# LPCB218_-_PARK_BRAKE.net
KiCad netlist of a schematic drawn in Altium Designer
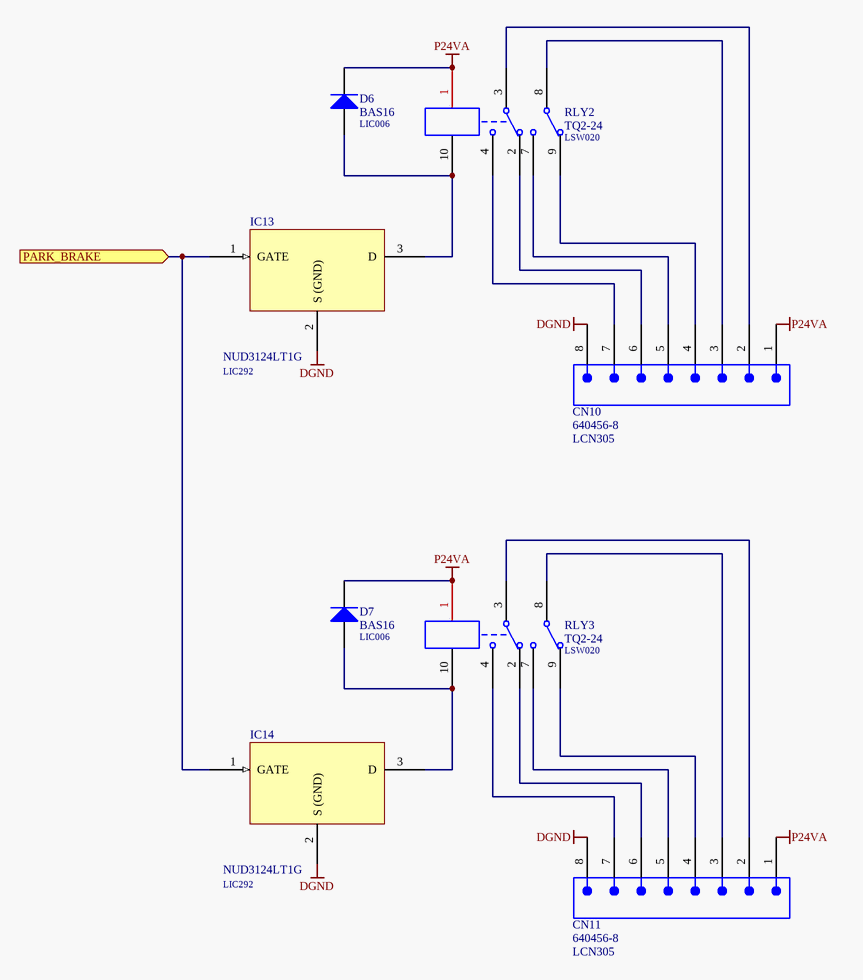
[diagram p0: LPCB218 - PARK BRAKE.SchDoc]

(export (version "E")
  (design (tool "Eeschema 10.0.6"))
  (components
    (comp (ref "CN10")
      (value "640456-8")
      (footprint "640456-8")
      (description "Connector, Male Header, 8 Way")
      (fields (field (name "LDL_NUMBER") "LCN305"))
      (libsource (lib "LDL_Connectors") (part "640456-8"))
    )
    (comp (ref "CN11")
      (value "640456-8")
      (footprint "640456-8")
      (description "Connector, Male Header, 8 Way")
      (fields (field (name "LDL_NUMBER") "LCN305"))
      (libsource (lib "LDL_Connectors") (part "640456-8"))
    )
    (comp (ref "D6")
      (value "BAS16")
      (footprint "LFP021__SOT23")
      (description "Diode, Small Signal, 0.2A, 85V, SMD SOT-23 [LIC006]")
      (fields (field (name "LDL_NUMBER") "LIC006"))
      (libsource (lib "LDL_Semiconductors") (part "BAS16"))
    )
    (comp (ref "D7")
      (value "BAS16")
      (footprint "LFP021__SOT23")
      (description "Diode, Small Signal, 0.2A, 85V, SMD SOT-23 [LIC006]")
      (fields (field (name "LDL_NUMBER") "LIC006"))
      (libsource (lib "LDL_Semiconductors") (part "BAS16"))
    )
    (comp (ref "IC13")
      (value "NUD3124LT1G")
      (footprint "LFP021__SOT23")
      (description "IC, Relay Driver, 28V Industrial, SMD SOT23 [LIC292]")
      (fields (field (name "LDL_NUMBER") "LIC292"))
      (libsource (lib "LDL_Semiconductors") (part "NUD3124LT1G"))
    )
    (comp (ref "IC14")
      (value "NUD3124LT1G")
      (footprint "LFP021__SOT23")
      (description "IC, Relay Driver, 28V Industrial, SMD SOT23 [LIC292]")
      (fields (field (name "LDL_NUMBER") "LIC292"))
      (libsource (lib "LDL_Semiconductors") (part "NUD3124LT1G"))
    )
    (comp (ref "RLY2")
      (value "TQ2-24")
      (footprint "TQ2")
      (description "Relay, DPDT, Non Latching, 24VDC Coil, 1A Rating, PTH")
      (fields (field (name "LDL_NUMBER") "LSW020"))
      (libsource (lib "LDL_Switching") (part "TQ2-24"))
    )
    (comp (ref "RLY3")
      (value "TQ2-24")
      (footprint "TQ2")
      (description "Relay, DPDT, Non Latching, 24VDC Coil, 1A Rating, PTH")
      (fields (field (name "LDL_NUMBER") "LSW020"))
      (libsource (lib "LDL_Switching") (part "TQ2-24"))
    )
  )
  (nets
    (net (code "1") (name "/PARK_BRAKE") (class "Default")
      (node (ref "IC13") (pin "1") (pinfunction "GATE_1") (pintype "input"))
      (node (ref "IC14") (pin "1") (pinfunction "GATE_1") (pintype "input"))
    )
    (net (code "2") (name "DGND") (class "Default")
      (node (ref "CN10") (pin "8") (pinfunction "8_8") (pintype "passive"))
      (node (ref "CN11") (pin "8") (pinfunction "8_8") (pintype "passive"))
      (node (ref "IC13") (pin "2") (pinfunction "S_(GND)_2") (pintype "passive"))
      (node (ref "IC14") (pin "2") (pinfunction "S_(GND)_2") (pintype "passive"))
    )
    (net (code "3") (name "Net-(CN10-Pad2)") (class "Default")
      (node (ref "CN10") (pin "2") (pinfunction "2_2") (pintype "passive"))
      (node (ref "RLY2") (pin "3") (pinfunction "3_3") (pintype "passive"))
    )
    (net (code "4") (name "Net-(CN10-Pad3)") (class "Default")
      (node (ref "CN10") (pin "3") (pinfunction "3_3") (pintype "passive"))
      (node (ref "RLY2") (pin "8") (pinfunction "8_8") (pintype "passive"))
    )
    (net (code "5") (name "Net-(CN10-Pad4)") (class "Default")
      (node (ref "CN10") (pin "4") (pinfunction "4_4") (pintype "passive"))
      (node (ref "RLY2") (pin "9") (pinfunction "9_9") (pintype "passive"))
    )
    (net (code "6") (name "Net-(CN10-Pad5)") (class "Default")
      (node (ref "CN10") (pin "5") (pinfunction "5_5") (pintype "passive"))
      (node (ref "RLY2") (pin "7") (pinfunction "7_7") (pintype "passive"))
    )
    (net (code "7") (name "Net-(CN10-Pad6)") (class "Default")
      (node (ref "CN10") (pin "6") (pinfunction "6_6") (pintype "passive"))
      (node (ref "RLY2") (pin "2") (pinfunction "2_2") (pintype "passive"))
    )
    (net (code "8") (name "Net-(CN10-Pad7)") (class "Default")
      (node (ref "CN10") (pin "7") (pinfunction "7_7") (pintype "passive"))
      (node (ref "RLY2") (pin "4") (pinfunction "4_4") (pintype "passive"))
    )
    (net (code "9") (name "Net-(CN11-Pad2)") (class "Default")
      (node (ref "CN11") (pin "2") (pinfunction "2_2") (pintype "passive"))
      (node (ref "RLY3") (pin "3") (pinfunction "3_3") (pintype "passive"))
    )
    (net (code "10") (name "Net-(CN11-Pad3)") (class "Default")
      (node (ref "CN11") (pin "3") (pinfunction "3_3") (pintype "passive"))
      (node (ref "RLY3") (pin "8") (pinfunction "8_8") (pintype "passive"))
    )
    (net (code "11") (name "Net-(CN11-Pad4)") (class "Default")
      (node (ref "CN11") (pin "4") (pinfunction "4_4") (pintype "passive"))
      (node (ref "RLY3") (pin "9") (pinfunction "9_9") (pintype "passive"))
    )
    (net (code "12") (name "Net-(CN11-Pad5)") (class "Default")
      (node (ref "CN11") (pin "5") (pinfunction "5_5") (pintype "passive"))
      (node (ref "RLY3") (pin "7") (pinfunction "7_7") (pintype "passive"))
    )
    (net (code "13") (name "Net-(CN11-Pad6)") (class "Default")
      (node (ref "CN11") (pin "6") (pinfunction "6_6") (pintype "passive"))
      (node (ref "RLY3") (pin "2") (pinfunction "2_2") (pintype "passive"))
    )
    (net (code "14") (name "Net-(CN11-Pad7)") (class "Default")
      (node (ref "CN11") (pin "7") (pinfunction "7_7") (pintype "passive"))
      (node (ref "RLY3") (pin "4") (pinfunction "4_4") (pintype "passive"))
    )
    (net (code "15") (name "Net-(D6-A)") (class "Default")
      (node (ref "D6") (pin "1") (pinfunction "A_1") (pintype "passive"))
      (node (ref "IC13") (pin "3") (pinfunction "D_3") (pintype "passive"))
      (node (ref "RLY2") (pin "10") (pinfunction "10_10") (pintype "passive"))
    )
    (net (code "16") (name "Net-(D7-A)") (class "Default")
      (node (ref "D7") (pin "1") (pinfunction "A_1") (pintype "passive"))
      (node (ref "IC14") (pin "3") (pinfunction "D_3") (pintype "passive"))
      (node (ref "RLY3") (pin "10") (pinfunction "10_10") (pintype "passive"))
    )
    (net (code "17") (name "P24VA") (class "Default")
      (node (ref "CN10") (pin "1") (pinfunction "1_1") (pintype "passive"))
      (node (ref "CN11") (pin "1") (pinfunction "1_1") (pintype "passive"))
      (node (ref "D6") (pin "3") (pinfunction "K_3") (pintype "passive"))
      (node (ref "D7") (pin "3") (pinfunction "K_3") (pintype "passive"))
      (node (ref "RLY2") (pin "1") (pinfunction "1_1") (pintype "passive"))
      (node (ref "RLY3") (pin "1") (pinfunction "1_1") (pintype "passive"))
    )
  )
)
